# LB_BIT_i15_LIGHTTRIGGER-v03_rev3_2x.net
KiCad netlist of a schematic drawn in EAGLE
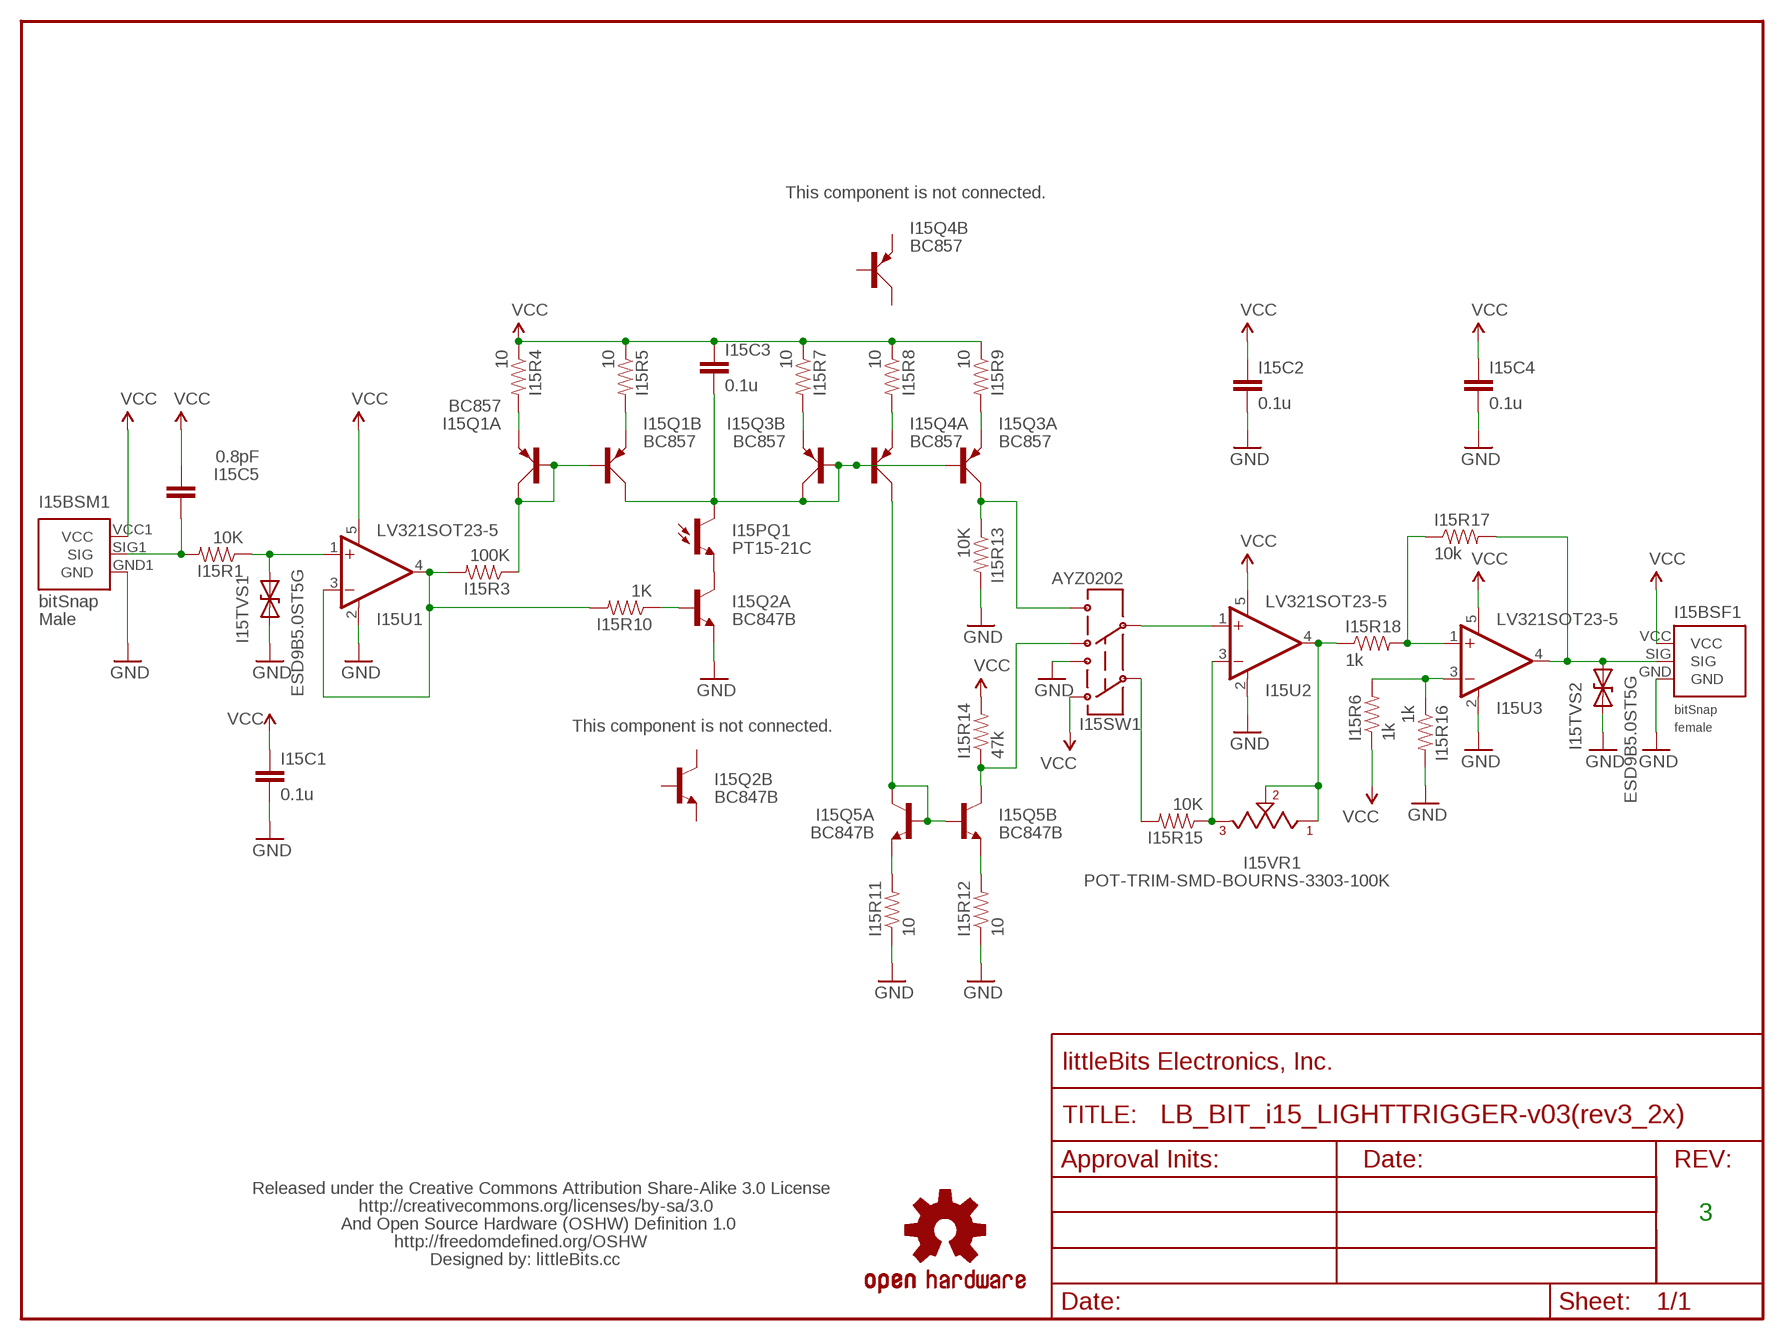
[diagram p0: schematic, sheet 1]

(export (version "E")
  (design (tool "Eeschema 10.0.6"))
  (components
    (comp (ref "FRAME1")
      (value "FRAME-LETTER-OHWOHW")
      (footprint "eagle-import:FABDWG01-OHW")
      (libsource (lib "eagle-import") (part "FRAME-LETTER-OHWOHW"))
    )
    (comp (ref "I15BSF1")
      (value "BITSNAP_V03_FEMALE")
      (footprint "eagle-import:BITSNAP_V03_FEMALE")
      (libsource (lib "eagle-import") (part "BITSNAP_V03_FEMALE"))
    )
    (comp (ref "I15BSM1")
      (value "BITSNAP_V03_MALE")
      (footprint "eagle-import:BITSNAP_V03_MALE")
      (libsource (lib "eagle-import") (part "BITSNAP_V03_MALE"))
    )
    (comp (ref "I15C1")
      (value "0.1u")
      (footprint "eagle-import:CAP-0603")
      (libsource (lib "eagle-import") (part "CAPCAP-0603"))
    )
    (comp (ref "I15C2")
      (value "0.1u")
      (footprint "eagle-import:CAP-0603")
      (libsource (lib "eagle-import") (part "CAPCAP-0603"))
    )
    (comp (ref "I15C3")
      (value "0.1u")
      (footprint "eagle-import:CAP-0603")
      (libsource (lib "eagle-import") (part "CAPCAP-0603"))
    )
    (comp (ref "I15C4")
      (value "0.1u")
      (footprint "eagle-import:CAP-0603")
      (libsource (lib "eagle-import") (part "CAPCAP-0603"))
    )
    (comp (ref "I15C5")
      (value "0.8pF")
      (footprint "eagle-import:CAP-0603")
      (libsource (lib "eagle-import") (part "CAPCAP-0603"))
    )
    (comp (ref "I15PQ1")
      (value "PT15-21C")
      (footprint "eagle-import:PHOTOTRANS-1206")
      (libsource (lib "eagle-import") (part "TRANS-PHOTO"))
    )
    (comp (ref "I15Q1")
      (value "BC857")
      (footprint "eagle-import:SOT-363_PHILLIPS")
      (libsource (lib "eagle-import") (part "TRANS-BJT_PNP-DUALBC857"))
    )
    (comp (ref "I15Q2")
      (value "BC847B")
      (footprint "eagle-import:SOT-363_PHILLIPS")
      (libsource (lib "eagle-import") (part "TRANS-BJT_NPN-DUALBC847BS"))
    )
    (comp (ref "I15Q3")
      (value "BC857")
      (footprint "eagle-import:SOT-363_PHILLIPS")
      (libsource (lib "eagle-import") (part "TRANS-BJT_PNP-DUALBC857"))
    )
    (comp (ref "I15Q4")
      (value "BC857")
      (footprint "eagle-import:SOT-363_PHILLIPS")
      (libsource (lib "eagle-import") (part "TRANS-BJT_PNP-DUALBC857"))
    )
    (comp (ref "I15Q5")
      (value "BC847B")
      (footprint "eagle-import:SOT-363_PHILLIPS")
      (libsource (lib "eagle-import") (part "TRANS-BJT_NPN-DUALBC847BS"))
    )
    (comp (ref "I15R1")
      (value "10K")
      (footprint "eagle-import:RES-0603")
      (libsource (lib "eagle-import") (part "RESISTOR0603"))
    )
    (comp (ref "I15R3")
      (value "100K")
      (footprint "eagle-import:RES-0603")
      (libsource (lib "eagle-import") (part "RESISTOR0603"))
    )
    (comp (ref "I15R4")
      (value "10")
      (footprint "eagle-import:RES-0603")
      (libsource (lib "eagle-import") (part "RESISTOR0603"))
    )
    (comp (ref "I15R5")
      (value "10")
      (footprint "eagle-import:RES-0603")
      (libsource (lib "eagle-import") (part "RESISTOR0603"))
    )
    (comp (ref "I15R6")
      (value "1k")
      (footprint "eagle-import:RES-0603")
      (libsource (lib "eagle-import") (part "RES-0603"))
    )
    (comp (ref "I15R7")
      (value "10")
      (footprint "eagle-import:RES-0603")
      (libsource (lib "eagle-import") (part "RESISTOR0603"))
    )
    (comp (ref "I15R8")
      (value "10")
      (footprint "eagle-import:RES-0603")
      (libsource (lib "eagle-import") (part "RESISTOR0603"))
    )
    (comp (ref "I15R9")
      (value "10")
      (footprint "eagle-import:RES-0603")
      (libsource (lib "eagle-import") (part "RESISTOR0603"))
    )
    (comp (ref "I15R10")
      (value "1K")
      (footprint "eagle-import:RES-0603")
      (libsource (lib "eagle-import") (part "RESISTOR0603"))
    )
    (comp (ref "I15R11")
      (value "10")
      (footprint "eagle-import:RES-0603")
      (libsource (lib "eagle-import") (part "RESISTOR0603"))
    )
    (comp (ref "I15R12")
      (value "10")
      (footprint "eagle-import:RES-0603")
      (libsource (lib "eagle-import") (part "RESISTOR0603"))
    )
    (comp (ref "I15R13")
      (value "10K")
      (footprint "eagle-import:RES-0603")
      (libsource (lib "eagle-import") (part "RESISTOR0603"))
    )
    (comp (ref "I15R14")
      (value "47k")
      (footprint "eagle-import:RES-0603")
      (libsource (lib "eagle-import") (part "RESISTOR0603"))
    )
    (comp (ref "I15R15")
      (value "10K")
      (footprint "eagle-import:RES-0603")
      (libsource (lib "eagle-import") (part "RES-0603"))
    )
    (comp (ref "I15R16")
      (value "1k")
      (footprint "eagle-import:RES-0603")
      (libsource (lib "eagle-import") (part "RES-0603"))
    )
    (comp (ref "I15R17")
      (value "10k")
      (footprint "eagle-import:RES-0603")
      (libsource (lib "eagle-import") (part "RES-0603"))
    )
    (comp (ref "I15R18")
      (value "1k")
      (footprint "eagle-import:RES-0603")
      (libsource (lib "eagle-import") (part "RES-0603"))
    )
    (comp (ref "I15SW1")
      (value "AYZ0202")
      (footprint "eagle-import:AYZ0202")
      (libsource (lib "eagle-import") (part "AYZ0202"))
    )
    (comp (ref "I15TVS1")
      (value "ESD9B5.0ST5G")
      (footprint "eagle-import:SOD-923")
      (libsource (lib "eagle-import") (part "DIODE-TVSSOD-923"))
    )
    (comp (ref "I15TVS2")
      (value "ESD9B5.0ST5G")
      (footprint "eagle-import:SOD-923")
      (libsource (lib "eagle-import") (part "DIODE-TVSSOD-923"))
    )
    (comp (ref "I15U1")
      (value "LV321SOT23-5")
      (footprint "eagle-import:SOT23-5")
      (libsource (lib "eagle-import") (part "LV321SOT23-5"))
    )
    (comp (ref "I15U2")
      (value "LV321SOT23-5")
      (footprint "eagle-import:SOT23-5")
      (libsource (lib "eagle-import") (part "LV321SOT23-5"))
    )
    (comp (ref "I15U3")
      (value "LV321SOT23-5")
      (footprint "eagle-import:SOT23-5")
      (libsource (lib "eagle-import") (part "LV321SOT23-5"))
    )
    (comp (ref "I15VR1")
      (value "POT-TRIM-SMD-BOURNS-3303-100K")
      (footprint "eagle-import:POT-TRIM-SMD-BOURNS-3303")
      (libsource (lib "eagle-import") (part "POT-TRIM-SMD-BOURNS-3303"))
    )
    (comp (ref "U$1")
      (value "OSHWCREDIT")
      (footprint "eagle-import:OSHWCREDIT")
      (libsource (lib "eagle-import") (part "OSHWCREDIT"))
    )
    (comp (ref "U$2")
      (value "OSHW-LOGOL")
      (footprint "eagle-import:OSHW-LOGO-L")
      (libsource (lib "eagle-import") (part "OSHW-LOGOL"))
    )
  )
  (nets
    (net (code "1") (name "GND") (class "Default")
      (node (ref "I15BSF1") (pin "GND") (pinfunction "GND_GND") (pintype "bidirectional"))
      (node (ref "I15BSM1") (pin "GND1") (pinfunction "GND_GND1") (pintype "bidirectional"))
      (node (ref "I15C1") (pin "2") (pinfunction "2_2") (pintype "passive"))
      (node (ref "I15C2") (pin "2") (pinfunction "2_2") (pintype "passive"))
      (node (ref "I15C4") (pin "2") (pinfunction "2_2") (pintype "passive"))
      (node (ref "I15Q2") (pin "1") (pinfunction "E_1") (pintype "passive"))
      (node (ref "I15R11") (pin "1") (pinfunction "1_1") (pintype "passive"))
      (node (ref "I15R12") (pin "1") (pinfunction "1_1") (pintype "passive"))
      (node (ref "I15R13") (pin "2") (pinfunction "2_2") (pintype "passive"))
      (node (ref "I15R16") (pin "2") (pinfunction "2_2") (pintype "passive"))
      (node (ref "I15SW1") (pin "3") (pinfunction "3_3") (pintype "bidirectional"))
      (node (ref "I15TVS1") (pin "1") (pinfunction "A_1") (pintype "passive"))
      (node (ref "I15TVS2") (pin "1") (pinfunction "A_1") (pintype "passive"))
      (node (ref "I15U1") (pin "2") (pinfunction "V-_2") (pintype "power_in"))
      (node (ref "I15U2") (pin "2") (pinfunction "V-_2") (pintype "power_in"))
      (node (ref "I15U3") (pin "2") (pinfunction "V-_2") (pintype "power_in"))
    )
    (net (code "2") (name "Net-(I15BSM1-SIG)") (class "Default")
      (node (ref "I15BSM1") (pin "SIG1") (pinfunction "SIG_SIG1") (pintype "bidirectional"))
      (node (ref "I15C5") (pin "1") (pinfunction "1_1") (pintype "passive"))
      (node (ref "I15R1") (pin "2") (pinfunction "2_2") (pintype "passive"))
    )
    (net (code "3") (name "Net-(I15Q1A-B)") (class "Default")
      (node (ref "I15Q1") (pin "2") (pinfunction "B_2") (pintype "passive"))
      (node (ref "I15Q1") (pin "5") (pinfunction "B_5") (pintype "passive"))
      (node (ref "I15Q1") (pin "6") (pinfunction "C_6") (pintype "passive"))
      (node (ref "I15R3") (pin "1") (pinfunction "1_1") (pintype "passive"))
    )
    (net (code "4") (name "Net-(I15Q1A-E)") (class "Default")
      (node (ref "I15Q1") (pin "1") (pinfunction "E_1") (pintype "passive"))
      (node (ref "I15R4") (pin "2") (pinfunction "2_2") (pintype "passive"))
    )
    (net (code "5") (name "Net-(I15Q1B-C)") (class "Default")
      (node (ref "I15C3") (pin "2") (pinfunction "2_2") (pintype "passive"))
      (node (ref "I15PQ1") (pin "C") (pinfunction "C_C") (pintype "passive"))
      (node (ref "I15Q1") (pin "3") (pinfunction "C_3") (pintype "passive"))
      (node (ref "I15Q3") (pin "2") (pinfunction "B_2") (pintype "passive"))
      (node (ref "I15Q3") (pin "3") (pinfunction "C_3") (pintype "passive"))
      (node (ref "I15Q3") (pin "5") (pinfunction "B_5") (pintype "passive"))
      (node (ref "I15Q4") (pin "2") (pinfunction "B_2") (pintype "passive"))
    )
    (net (code "6") (name "Net-(I15Q1B-E)") (class "Default")
      (node (ref "I15Q1") (pin "4") (pinfunction "E_4") (pintype "passive"))
      (node (ref "I15R5") (pin "2") (pinfunction "2_2") (pintype "passive"))
    )
    (net (code "7") (name "Net-(I15Q2A-B)") (class "Default")
      (node (ref "I15Q2") (pin "2") (pinfunction "B_2") (pintype "passive"))
      (node (ref "I15R10") (pin "1") (pinfunction "1_1") (pintype "passive"))
    )
    (net (code "8") (name "Net-(I15Q2A-C)") (class "Default")
      (node (ref "I15PQ1") (pin "E") (pinfunction "E_E") (pintype "passive"))
      (node (ref "I15Q2") (pin "6") (pinfunction "C_6") (pintype "passive"))
    )
    (net (code "9") (name "Net-(I15Q3A-C)") (class "Default")
      (node (ref "I15Q3") (pin "6") (pinfunction "C_6") (pintype "passive"))
      (node (ref "I15R13") (pin "1") (pinfunction "1_1") (pintype "passive"))
      (node (ref "I15SW1") (pin "6") (pinfunction "6_6") (pintype "bidirectional"))
    )
    (net (code "10") (name "Net-(I15Q3A-E)") (class "Default")
      (node (ref "I15Q3") (pin "1") (pinfunction "E_1") (pintype "passive"))
      (node (ref "I15R9") (pin "2") (pinfunction "2_2") (pintype "passive"))
    )
    (net (code "11") (name "Net-(I15Q3B-E)") (class "Default")
      (node (ref "I15Q3") (pin "4") (pinfunction "E_4") (pintype "passive"))
      (node (ref "I15R7") (pin "2") (pinfunction "2_2") (pintype "passive"))
    )
    (net (code "12") (name "Net-(I15Q4A-C)") (class "Default")
      (node (ref "I15Q4") (pin "6") (pinfunction "C_6") (pintype "passive"))
      (node (ref "I15Q5") (pin "2") (pinfunction "B_2") (pintype "passive"))
      (node (ref "I15Q5") (pin "5") (pinfunction "B_5") (pintype "passive"))
      (node (ref "I15Q5") (pin "6") (pinfunction "C_6") (pintype "passive"))
    )
    (net (code "13") (name "Net-(I15Q4A-E)") (class "Default")
      (node (ref "I15Q4") (pin "1") (pinfunction "E_1") (pintype "passive"))
      (node (ref "I15R8") (pin "2") (pinfunction "2_2") (pintype "passive"))
    )
    (net (code "14") (name "Net-(I15Q5A-E)") (class "Default")
      (node (ref "I15Q5") (pin "1") (pinfunction "E_1") (pintype "passive"))
      (node (ref "I15R11") (pin "2") (pinfunction "2_2") (pintype "passive"))
    )
    (net (code "15") (name "Net-(I15Q5B-C)") (class "Default")
      (node (ref "I15Q5") (pin "3") (pinfunction "C_3") (pintype "passive"))
      (node (ref "I15R14") (pin "1") (pinfunction "1_1") (pintype "passive"))
      (node (ref "I15SW1") (pin "4") (pinfunction "4_4") (pintype "bidirectional"))
    )
    (net (code "16") (name "Net-(I15Q5B-E)") (class "Default")
      (node (ref "I15Q5") (pin "4") (pinfunction "E_4") (pintype "passive"))
      (node (ref "I15R12") (pin "2") (pinfunction "2_2") (pintype "passive"))
    )
    (net (code "17") (name "Net-(I15R15-Pad2)") (class "Default")
      (node (ref "I15R15") (pin "2") (pinfunction "2_2") (pintype "passive"))
      (node (ref "I15SW1") (pin "2") (pinfunction "2_2") (pintype "bidirectional"))
    )
    (net (code "18") (name "Net-(I15TVS1-C)") (class "Default")
      (node (ref "I15R1") (pin "1") (pinfunction "1_1") (pintype "passive"))
      (node (ref "I15TVS1") (pin "2") (pinfunction "C_2") (pintype "passive"))
      (node (ref "I15U1") (pin "1") (pinfunction "+IN_1") (pintype "input"))
    )
    (net (code "19") (name "Net-(I15TVS2-C)") (class "Default")
      (node (ref "I15BSF1") (pin "SIG") (pinfunction "SIG_SIG") (pintype "bidirectional"))
      (node (ref "I15R17") (pin "2") (pinfunction "2_2") (pintype "passive"))
      (node (ref "I15TVS2") (pin "2") (pinfunction "C_2") (pintype "passive"))
      (node (ref "I15U3") (pin "4") (pinfunction "OUT_4") (pintype "output"))
    )
    (net (code "20") (name "Net-(I15U1--IN)") (class "Default")
      (node (ref "I15R10") (pin "2") (pinfunction "2_2") (pintype "passive"))
      (node (ref "I15R3") (pin "2") (pinfunction "2_2") (pintype "passive"))
      (node (ref "I15U1") (pin "3") (pinfunction "-IN_3") (pintype "input"))
      (node (ref "I15U1") (pin "4") (pinfunction "OUT_4") (pintype "output"))
    )
    (net (code "21") (name "Net-(I15U2-+IN)") (class "Default")
      (node (ref "I15SW1") (pin "5") (pinfunction "5_5") (pintype "bidirectional"))
      (node (ref "I15U2") (pin "1") (pinfunction "+IN_1") (pintype "input"))
    )
    (net (code "22") (name "Net-(I15U2--IN)") (class "Default")
      (node (ref "I15R15") (pin "1") (pinfunction "1_1") (pintype "passive"))
      (node (ref "I15U2") (pin "3") (pinfunction "-IN_3") (pintype "input"))
      (node (ref "I15VR1") (pin "3") (pinfunction "3_3") (pintype "passive"))
    )
    (net (code "23") (name "Net-(I15U2-OUT)") (class "Default")
      (node (ref "I15R18") (pin "1") (pinfunction "1_1") (pintype "passive"))
      (node (ref "I15U2") (pin "4") (pinfunction "OUT_4") (pintype "output"))
      (node (ref "I15VR1") (pin "1") (pinfunction "1_1") (pintype "passive"))
      (node (ref "I15VR1") (pin "2") (pinfunction "2_2") (pintype "passive"))
    )
    (net (code "24") (name "Net-(I15U3-+IN)") (class "Default")
      (node (ref "I15R17") (pin "1") (pinfunction "1_1") (pintype "passive"))
      (node (ref "I15R18") (pin "2") (pinfunction "2_2") (pintype "passive"))
      (node (ref "I15U3") (pin "1") (pinfunction "+IN_1") (pintype "input"))
    )
    (net (code "25") (name "Net-(I15U3--IN)") (class "Default")
      (node (ref "I15R16") (pin "1") (pinfunction "1_1") (pintype "passive"))
      (node (ref "I15R6") (pin "2") (pinfunction "2_2") (pintype "passive"))
      (node (ref "I15U3") (pin "3") (pinfunction "-IN_3") (pintype "input"))
    )
    (net (code "26") (name "VCC") (class "Default")
      (node (ref "I15BSF1") (pin "VCC") (pinfunction "VCC_VCC") (pintype "bidirectional"))
      (node (ref "I15BSM1") (pin "VCC1") (pinfunction "VCC_VCC1") (pintype "bidirectional"))
      (node (ref "I15C1") (pin "1") (pinfunction "1_1") (pintype "passive"))
      (node (ref "I15C2") (pin "1") (pinfunction "1_1") (pintype "passive"))
      (node (ref "I15C3") (pin "1") (pinfunction "1_1") (pintype "passive"))
      (node (ref "I15C4") (pin "1") (pinfunction "1_1") (pintype "passive"))
      (node (ref "I15C5") (pin "2") (pinfunction "2_2") (pintype "passive"))
      (node (ref "I15R14") (pin "2") (pinfunction "2_2") (pintype "passive"))
      (node (ref "I15R4") (pin "1") (pinfunction "1_1") (pintype "passive"))
      (node (ref "I15R5") (pin "1") (pinfunction "1_1") (pintype "passive"))
      (node (ref "I15R6") (pin "1") (pinfunction "1_1") (pintype "passive"))
      (node (ref "I15R7") (pin "1") (pinfunction "1_1") (pintype "passive"))
      (node (ref "I15R8") (pin "1") (pinfunction "1_1") (pintype "passive"))
      (node (ref "I15R9") (pin "1") (pinfunction "1_1") (pintype "passive"))
      (node (ref "I15SW1") (pin "1") (pinfunction "1_1") (pintype "bidirectional"))
      (node (ref "I15U1") (pin "5") (pinfunction "V+_5") (pintype "power_in"))
      (node (ref "I15U2") (pin "5") (pinfunction "V+_5") (pintype "power_in"))
      (node (ref "I15U3") (pin "5") (pinfunction "V+_5") (pintype "power_in"))
    )
    (net (code "27") (name "unconnected-(I15Q2B-B-Pad5)") (class "Default")
      (node (ref "I15Q2") (pin "5") (pinfunction "B_5") (pintype "passive"))
    )
    (net (code "28") (name "unconnected-(I15Q2B-C-Pad3)") (class "Default")
      (node (ref "I15Q2") (pin "3") (pinfunction "C_3") (pintype "passive"))
    )
    (net (code "29") (name "unconnected-(I15Q2B-E-Pad4)") (class "Default")
      (node (ref "I15Q2") (pin "4") (pinfunction "E_4") (pintype "passive"))
    )
    (net (code "30") (name "unconnected-(I15Q4B-B-Pad5)") (class "Default")
      (node (ref "I15Q4") (pin "5") (pinfunction "B_5") (pintype "passive"))
    )
    (net (code "31") (name "unconnected-(I15Q4B-C-Pad3)") (class "Default")
      (node (ref "I15Q4") (pin "3") (pinfunction "C_3") (pintype "passive"))
    )
    (net (code "32") (name "unconnected-(I15Q4B-E-Pad4)") (class "Default")
      (node (ref "I15Q4") (pin "4") (pinfunction "E_4") (pintype "passive"))
    )
  )
)
